# Thermistors.net
KiCad netlist of a schematic drawn in Altium Designer
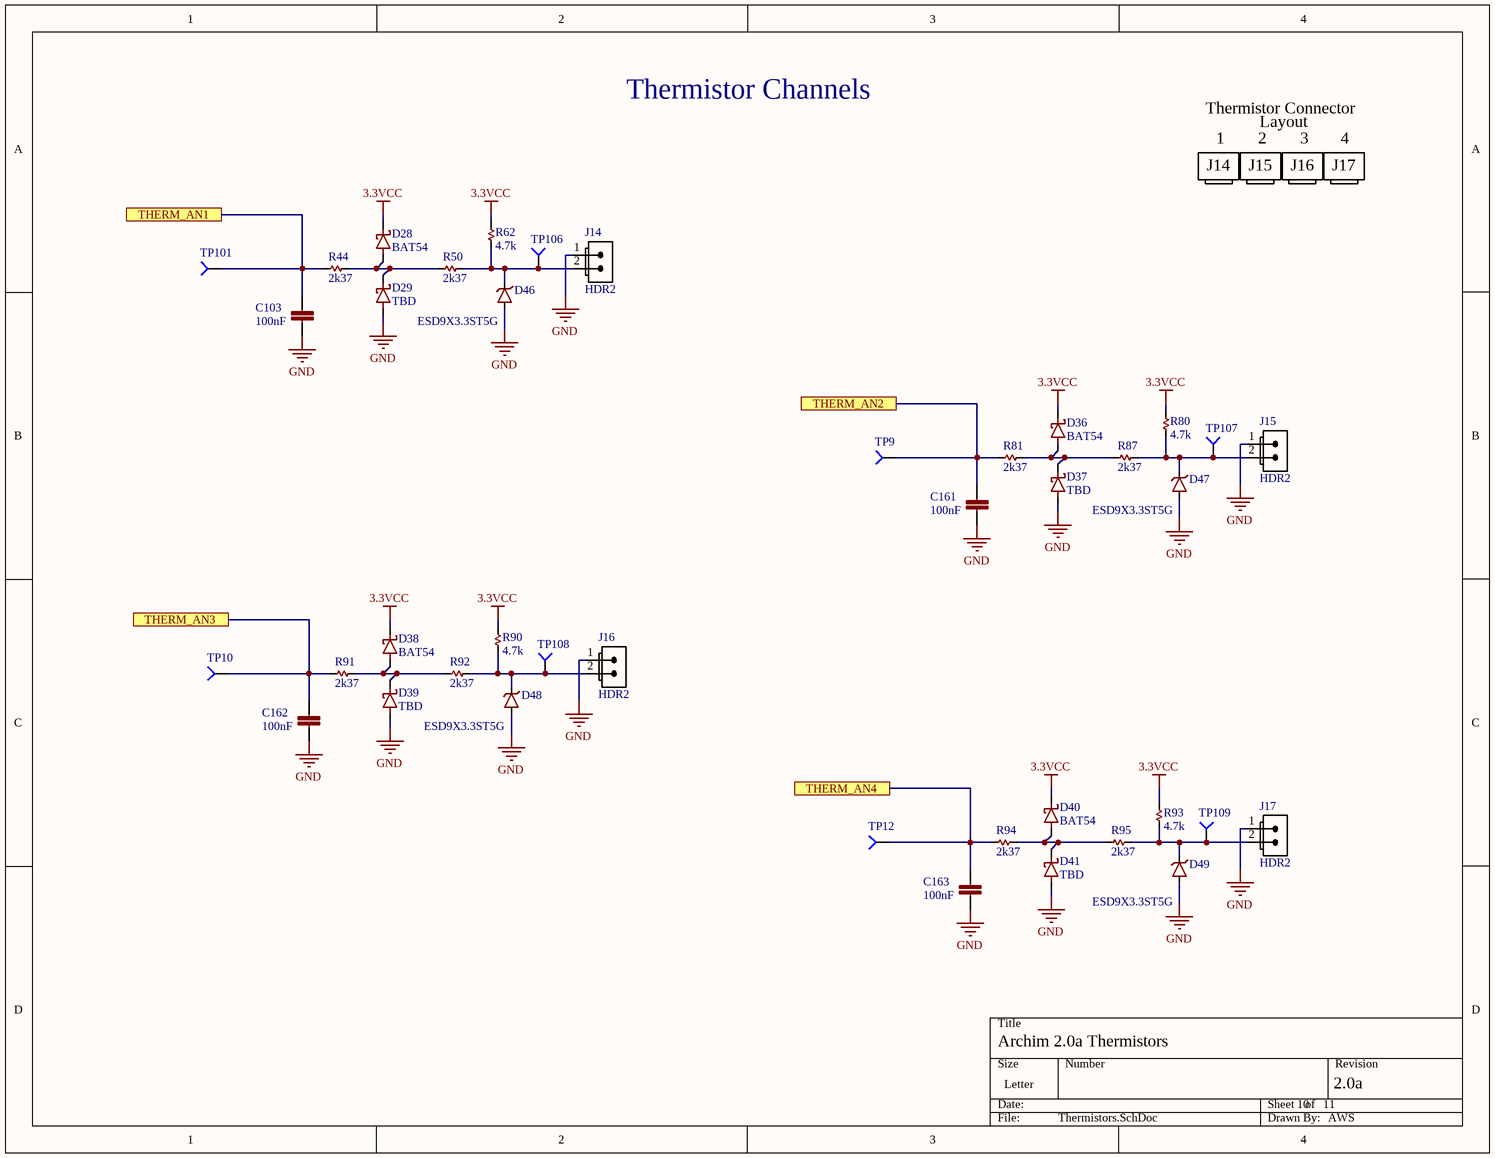
[diagram p0: Thermistors.SchDoc]

(export (version "E")
  (design (tool "Eeschema 10.0.6"))
  (components
    (comp (ref "C103")
      (value "100nF")
      (footprint "C0402")
      (description "CAP CER 0402 100nF 16V 10% X7R")
      (fields (field (name "MANUFACTURER") "Murata") (field (name "PART") "0.1uF 16V X7R 0402"))
      (libsource (lib "3Delight") (part "GRM155R71C104KA88D"))
    )
    (comp (ref "C161")
      (value "100nF")
      (footprint "C0402")
      (description "CAP CER 0402 100nF 16V 10% X7R")
      (fields (field (name "MANUFACTURER") "Murata") (field (name "PART") "0.1uF 16V X7R 0402"))
      (libsource (lib "3Delight") (part "GRM155R71C104KA88D"))
    )
    (comp (ref "C162")
      (value "100nF")
      (footprint "C0402")
      (description "CAP CER 0402 100nF 16V 10% X7R")
      (fields (field (name "MANUFACTURER") "Murata") (field (name "PART") "0.1uF 16V X7R 0402"))
      (libsource (lib "3Delight") (part "GRM155R71C104KA88D"))
    )
    (comp (ref "C163")
      (value "100nF")
      (footprint "C0402")
      (description "CAP CER 0402 100nF 16V 10% X7R")
      (fields (field (name "MANUFACTURER") "Murata") (field (name "PART") "0.1uF 16V X7R 0402"))
      (libsource (lib "3Delight") (part "GRM155R71C104KA88D"))
    )
    (comp (ref "D28")
      (value "BAT54")
      (footprint "SOD523_IPC")
      (description "DIODE SCHOTTKY 30V 200MA SOD523")
      (fields (field (name "MANUFACTURER") "Diodes Incorporated") (field (name "PART") "Schottky Diode"))
      (libsource (lib "Diodes") (part "BAT54WX"))
    )
    (comp (ref "D29")
      (value "TBD")
      (footprint "SOD523_IPC")
      (fields (field (name "TOLERANCE") "-NA-"))
      (libsource (lib "Diodes") (part "SOD523_TBD"))
    )
    (comp (ref "D36")
      (value "BAT54")
      (footprint "SOD523_IPC")
      (description "DIODE SCHOTTKY 30V 200MA SOD523")
      (fields (field (name "MANUFACTURER") "Diodes Incorporated") (field (name "PART") "Schottky Diode"))
      (libsource (lib "Diodes") (part "BAT54WX"))
    )
    (comp (ref "D37")
      (value "TBD")
      (footprint "SOD523_IPC")
      (fields (field (name "TOLERANCE") "-NA-"))
      (libsource (lib "Diodes") (part "SOD523_TBD"))
    )
    (comp (ref "D38")
      (value "BAT54")
      (footprint "SOD523_IPC")
      (description "DIODE SCHOTTKY 30V 200MA SOD523")
      (fields (field (name "MANUFACTURER") "Diodes Incorporated") (field (name "PART") "Schottky Diode"))
      (libsource (lib "Diodes") (part "BAT54WX"))
    )
    (comp (ref "D39")
      (value "TBD")
      (footprint "SOD523_IPC")
      (fields (field (name "TOLERANCE") "-NA-"))
      (libsource (lib "Diodes") (part "SOD523_TBD"))
    )
    (comp (ref "D40")
      (value "BAT54")
      (footprint "SOD523_IPC")
      (description "DIODE SCHOTTKY 30V 200MA SOD523")
      (fields (field (name "MANUFACTURER") "Diodes Incorporated") (field (name "PART") "Schottky Diode"))
      (libsource (lib "Diodes") (part "BAT54WX"))
    )
    (comp (ref "D41")
      (value "TBD")
      (footprint "SOD523_IPC")
      (fields (field (name "TOLERANCE") "-NA-"))
      (libsource (lib "Diodes") (part "SOD523_TBD"))
    )
    (comp (ref "D46")
      (value "ESD9X3.3ST5G")
      (footprint "SOD923-D")
      (description "TVS DIODE 3.3VWM 10.4VC SOD923")
      (fields (field (name "MANUFACTURER") "On Semi") (field (name "TOLERANCE") "-NA-"))
      (libsource (lib "Diodes") (part "ESD9X3.3ST5G"))
    )
    (comp (ref "D47")
      (value "ESD9X3.3ST5G")
      (footprint "SOD923-D")
      (description "TVS DIODE 3.3VWM 10.4VC SOD923")
      (fields (field (name "MANUFACTURER") "On Semi") (field (name "TOLERANCE") "-NA-"))
      (libsource (lib "Diodes") (part "ESD9X3.3ST5G"))
    )
    (comp (ref "D48")
      (value "ESD9X3.3ST5G")
      (footprint "SOD923-D")
      (description "TVS DIODE 3.3VWM 10.4VC SOD923")
      (fields (field (name "MANUFACTURER") "On Semi") (field (name "TOLERANCE") "-NA-"))
      (libsource (lib "Diodes") (part "ESD9X3.3ST5G"))
    )
    (comp (ref "D49")
      (value "ESD9X3.3ST5G")
      (footprint "SOD923-D")
      (description "TVS DIODE 3.3VWM 10.4VC SOD923")
      (fields (field (name "MANUFACTURER") "On Semi") (field (name "TOLERANCE") "-NA-"))
      (libsource (lib "Diodes") (part "ESD9X3.3ST5G"))
    )
    (comp (ref "J14")
      (value "HDR2")
      (footprint "70543-01 PIN-IN-PASTE")
      (description "Connector 2pos - Pin in Paste")
      (fields (field (name "MANUFACTURER") "Molex") (field (name "PART") "2 Pin Conn"))
      (libsource (lib "Connectors") (part "CONN 2PIN VERT 0.1{dblquote} SHRD LOCKING PIP"))
    )
    (comp (ref "J15")
      (value "HDR2")
      (footprint "70543-01 PIN-IN-PASTE")
      (description "Connector 2pos - Pin in Paste")
      (fields (field (name "MANUFACTURER") "Molex") (field (name "PART") "2 Pin Conn"))
      (libsource (lib "Connectors") (part "CONN 2PIN VERT 0.1{dblquote} SHRD LOCKING PIP"))
    )
    (comp (ref "J16")
      (value "HDR2")
      (footprint "70543-01 PIN-IN-PASTE")
      (description "Connector 2pos - Pin in Paste")
      (fields (field (name "MANUFACTURER") "Molex") (field (name "PART") "2 Pin Conn"))
      (libsource (lib "Connectors") (part "CONN 2PIN VERT 0.1{dblquote} SHRD LOCKING PIP"))
    )
    (comp (ref "J17")
      (value "HDR2")
      (footprint "70543-01 PIN-IN-PASTE")
      (description "Connector 2pos - Pin in Paste")
      (fields (field (name "MANUFACTURER") "Molex") (field (name "PART") "2 Pin Conn"))
      (libsource (lib "Connectors") (part "CONN 2PIN VERT 0.1{dblquote} SHRD LOCKING PIP"))
    )
    (comp (ref "R44")
      (value "2k37")
      (footprint "R0402")
      (description "RES SMD 2.37K OHM 1% 1/16W 0402")
      (fields (field (name "MANUFACTURER") "Yageo") (field (name "PART") "2.37k 1% 0402"))
      (libsource (lib "3Delight") (part "RC0402FR-072K37L"))
    )
    (comp (ref "R50")
      (value "2k37")
      (footprint "R0402")
      (description "RES SMD 2.37K OHM 1% 1/16W 0402")
      (fields (field (name "MANUFACTURER") "Yageo") (field (name "PART") "2.37k 1% 0402"))
      (libsource (lib "3Delight") (part "RC0402FR-072K37L"))
    )
    (comp (ref "R62")
      (value "4.7k")
      (footprint "R0402")
      (description "RES SMD 4.7K OHM 1% 1/16W 0402")
      (fields (field (name "MANUFACTURER") "YAGEO") (field (name "PART") "4.7k 1% 0402"))
      (libsource (lib "3Delight") (part "RC0402FR-074K7L"))
    )
    (comp (ref "R80")
      (value "4.7k")
      (footprint "R0402")
      (description "RES SMD 4.7K OHM 1% 1/16W 0402")
      (fields (field (name "MANUFACTURER") "YAGEO") (field (name "PART") "4.7k 1% 0402"))
      (libsource (lib "3Delight") (part "RC0402FR-074K7L"))
    )
    (comp (ref "R81")
      (value "2k37")
      (footprint "R0402")
      (description "RES SMD 2.37K OHM 1% 1/16W 0402")
      (fields (field (name "MANUFACTURER") "Yageo") (field (name "PART") "2.37k 1% 0402"))
      (libsource (lib "3Delight") (part "RC0402FR-072K37L"))
    )
    (comp (ref "R87")
      (value "2k37")
      (footprint "R0402")
      (description "RES SMD 2.37K OHM 1% 1/16W 0402")
      (fields (field (name "MANUFACTURER") "Yageo") (field (name "PART") "2.37k 1% 0402"))
      (libsource (lib "3Delight") (part "RC0402FR-072K37L"))
    )
    (comp (ref "R90")
      (value "4.7k")
      (footprint "R0402")
      (description "RES SMD 4.7K OHM 1% 1/16W 0402")
      (fields (field (name "MANUFACTURER") "YAGEO") (field (name "PART") "4.7k 1% 0402"))
      (libsource (lib "3Delight") (part "RC0402FR-074K7L"))
    )
    (comp (ref "R91")
      (value "2k37")
      (footprint "R0402")
      (description "RES SMD 2.37K OHM 1% 1/16W 0402")
      (fields (field (name "MANUFACTURER") "Yageo") (field (name "PART") "2.37k 1% 0402"))
      (libsource (lib "3Delight") (part "RC0402FR-072K37L"))
    )
    (comp (ref "R92")
      (value "2k37")
      (footprint "R0402")
      (description "RES SMD 2.37K OHM 1% 1/16W 0402")
      (fields (field (name "MANUFACTURER") "Yageo") (field (name "PART") "2.37k 1% 0402"))
      (libsource (lib "3Delight") (part "RC0402FR-072K37L"))
    )
    (comp (ref "R93")
      (value "4.7k")
      (footprint "R0402")
      (description "RES SMD 4.7K OHM 1% 1/16W 0402")
      (fields (field (name "MANUFACTURER") "YAGEO") (field (name "PART") "4.7k 1% 0402"))
      (libsource (lib "3Delight") (part "RC0402FR-074K7L"))
    )
    (comp (ref "R94")
      (value "2k37")
      (footprint "R0402")
      (description "RES SMD 2.37K OHM 1% 1/16W 0402")
      (fields (field (name "MANUFACTURER") "Yageo") (field (name "PART") "2.37k 1% 0402"))
      (libsource (lib "3Delight") (part "RC0402FR-072K37L"))
    )
    (comp (ref "R95")
      (value "2k37")
      (footprint "R0402")
      (description "RES SMD 2.37K OHM 1% 1/16W 0402")
      (fields (field (name "MANUFACTURER") "Yageo") (field (name "PART") "2.37k 1% 0402"))
      (libsource (lib "3Delight") (part "RC0402FR-072K37L"))
    )
    (comp (ref "TP9")
      (value "TP4")
      (footprint "TP-2")
      (description "Socket")
      (libsource (lib "Archim") (part "Socket"))
    )
    (comp (ref "TP10")
      (value "TP4")
      (footprint "TP-2")
      (description "Socket")
      (libsource (lib "Archim") (part "Socket"))
    )
    (comp (ref "TP12")
      (value "TP4")
      (footprint "TP-2")
      (description "Socket")
      (libsource (lib "Archim") (part "Socket"))
    )
    (comp (ref "TP101")
      (value "TP4")
      (footprint "TP-2")
      (description "Socket")
      (libsource (lib "Archim") (part "Socket"))
    )
    (comp (ref "TP106")
      (value "TP4")
      (footprint "TP-2")
      (description "Socket")
      (libsource (lib "Archim") (part "Socket"))
    )
    (comp (ref "TP107")
      (value "TP4")
      (footprint "TP-2")
      (description "Socket")
      (libsource (lib "Archim") (part "Socket"))
    )
    (comp (ref "TP108")
      (value "TP4")
      (footprint "TP-2")
      (description "Socket")
      (libsource (lib "Archim") (part "Socket"))
    )
    (comp (ref "TP109")
      (value "TP4")
      (footprint "TP-2")
      (description "Socket")
      (libsource (lib "Archim") (part "Socket"))
    )
  )
  (nets
    (net (code "1") (name "/THERM_AN1") (class "Default")
      (node (ref "C103") (pin "1") (pinfunction "1_1") (pintype "passive"))
      (node (ref "R44") (pin "1") (pinfunction "1_1") (pintype "passive"))
      (node (ref "TP101") (pin "1") (pinfunction "1_1") (pintype "passive"))
    )
    (net (code "2") (name "/THERM_AN2") (class "Default")
      (node (ref "C161") (pin "1") (pinfunction "1_1") (pintype "passive"))
      (node (ref "R81") (pin "1") (pinfunction "1_1") (pintype "passive"))
      (node (ref "TP9") (pin "1") (pinfunction "1_1") (pintype "passive"))
    )
    (net (code "3") (name "/THERM_AN3") (class "Default")
      (node (ref "C162") (pin "1") (pinfunction "1_1") (pintype "passive"))
      (node (ref "R91") (pin "1") (pinfunction "1_1") (pintype "passive"))
      (node (ref "TP10") (pin "1") (pinfunction "1_1") (pintype "passive"))
    )
    (net (code "4") (name "/THERM_AN4") (class "Default")
      (node (ref "C163") (pin "1") (pinfunction "1_1") (pintype "passive"))
      (node (ref "R94") (pin "1") (pinfunction "1_1") (pintype "passive"))
      (node (ref "TP12") (pin "1") (pinfunction "1_1") (pintype "passive"))
    )
    (net (code "5") (name "3.3VCC") (class "Default")
      (node (ref "D28") (pin "K") (pinfunction "K_K") (pintype "passive"))
      (node (ref "D36") (pin "K") (pinfunction "K_K") (pintype "passive"))
      (node (ref "D38") (pin "K") (pinfunction "K_K") (pintype "passive"))
      (node (ref "D40") (pin "K") (pinfunction "K_K") (pintype "passive"))
      (node (ref "R62") (pin "2") (pinfunction "2_2") (pintype "passive"))
      (node (ref "R80") (pin "2") (pinfunction "2_2") (pintype "passive"))
      (node (ref "R90") (pin "2") (pinfunction "2_2") (pintype "passive"))
      (node (ref "R93") (pin "2") (pinfunction "2_2") (pintype "passive"))
    )
    (net (code "6") (name "GND") (class "Default")
      (node (ref "C103") (pin "2") (pinfunction "2_2") (pintype "passive"))
      (node (ref "C161") (pin "2") (pinfunction "2_2") (pintype "passive"))
      (node (ref "C162") (pin "2") (pinfunction "2_2") (pintype "passive"))
      (node (ref "C163") (pin "2") (pinfunction "2_2") (pintype "passive"))
      (node (ref "D29") (pin "A") (pinfunction "A_A") (pintype "passive"))
      (node (ref "D37") (pin "A") (pinfunction "A_A") (pintype "passive"))
      (node (ref "D39") (pin "A") (pinfunction "A_A") (pintype "passive"))
      (node (ref "D41") (pin "A") (pinfunction "A_A") (pintype "passive"))
      (node (ref "D46") (pin "A") (pinfunction "A_A") (pintype "passive"))
      (node (ref "D47") (pin "A") (pinfunction "A_A") (pintype "passive"))
      (node (ref "D48") (pin "A") (pinfunction "A_A") (pintype "passive"))
      (node (ref "D49") (pin "A") (pinfunction "A_A") (pintype "passive"))
      (node (ref "J14") (pin "1") (pinfunction "S_1") (pintype "passive"))
      (node (ref "J15") (pin "1") (pinfunction "S_1") (pintype "passive"))
      (node (ref "J16") (pin "1") (pinfunction "S_1") (pintype "passive"))
      (node (ref "J17") (pin "1") (pinfunction "S_1") (pintype "passive"))
    )
    (net (code "7") (name "Net-(D28-PadA)") (class "Default")
      (node (ref "D28") (pin "A") (pinfunction "A_A") (pintype "passive"))
      (node (ref "D29") (pin "K") (pinfunction "K_K") (pintype "passive"))
      (node (ref "R44") (pin "2") (pinfunction "2_2") (pintype "passive"))
      (node (ref "R50") (pin "1") (pinfunction "1_1") (pintype "passive"))
    )
    (net (code "8") (name "Net-(D36-PadA)") (class "Default")
      (node (ref "D36") (pin "A") (pinfunction "A_A") (pintype "passive"))
      (node (ref "D37") (pin "K") (pinfunction "K_K") (pintype "passive"))
      (node (ref "R81") (pin "2") (pinfunction "2_2") (pintype "passive"))
      (node (ref "R87") (pin "1") (pinfunction "1_1") (pintype "passive"))
    )
    (net (code "9") (name "Net-(D38-PadA)") (class "Default")
      (node (ref "D38") (pin "A") (pinfunction "A_A") (pintype "passive"))
      (node (ref "D39") (pin "K") (pinfunction "K_K") (pintype "passive"))
      (node (ref "R91") (pin "2") (pinfunction "2_2") (pintype "passive"))
      (node (ref "R92") (pin "1") (pinfunction "1_1") (pintype "passive"))
    )
    (net (code "10") (name "Net-(D40-PadA)") (class "Default")
      (node (ref "D40") (pin "A") (pinfunction "A_A") (pintype "passive"))
      (node (ref "D41") (pin "K") (pinfunction "K_K") (pintype "passive"))
      (node (ref "R94") (pin "2") (pinfunction "2_2") (pintype "passive"))
      (node (ref "R95") (pin "1") (pinfunction "1_1") (pintype "passive"))
    )
    (net (code "11") (name "Net-(D46-PadK)") (class "Default")
      (node (ref "D46") (pin "K") (pinfunction "K_K") (pintype "passive"))
      (node (ref "J14") (pin "2") (pinfunction "S_2") (pintype "passive"))
      (node (ref "R50") (pin "2") (pinfunction "2_2") (pintype "passive"))
      (node (ref "R62") (pin "1") (pinfunction "1_1") (pintype "passive"))
      (node (ref "TP106") (pin "1") (pinfunction "1_1") (pintype "passive"))
    )
    (net (code "12") (name "Net-(D47-PadK)") (class "Default")
      (node (ref "D47") (pin "K") (pinfunction "K_K") (pintype "passive"))
      (node (ref "J15") (pin "2") (pinfunction "S_2") (pintype "passive"))
      (node (ref "R80") (pin "1") (pinfunction "1_1") (pintype "passive"))
      (node (ref "R87") (pin "2") (pinfunction "2_2") (pintype "passive"))
      (node (ref "TP107") (pin "1") (pinfunction "1_1") (pintype "passive"))
    )
    (net (code "13") (name "Net-(D48-PadK)") (class "Default")
      (node (ref "D48") (pin "K") (pinfunction "K_K") (pintype "passive"))
      (node (ref "J16") (pin "2") (pinfunction "S_2") (pintype "passive"))
      (node (ref "R90") (pin "1") (pinfunction "1_1") (pintype "passive"))
      (node (ref "R92") (pin "2") (pinfunction "2_2") (pintype "passive"))
      (node (ref "TP108") (pin "1") (pinfunction "1_1") (pintype "passive"))
    )
    (net (code "14") (name "Net-(D49-PadK)") (class "Default")
      (node (ref "D49") (pin "K") (pinfunction "K_K") (pintype "passive"))
      (node (ref "J17") (pin "2") (pinfunction "S_2") (pintype "passive"))
      (node (ref "R93") (pin "1") (pinfunction "1_1") (pintype "passive"))
      (node (ref "R95") (pin "2") (pinfunction "2_2") (pintype "passive"))
      (node (ref "TP109") (pin "1") (pinfunction "1_1") (pintype "passive"))
    )
  )
)
